# Sheet1.net
KiCad netlist of a schematic drawn in Altium Designer
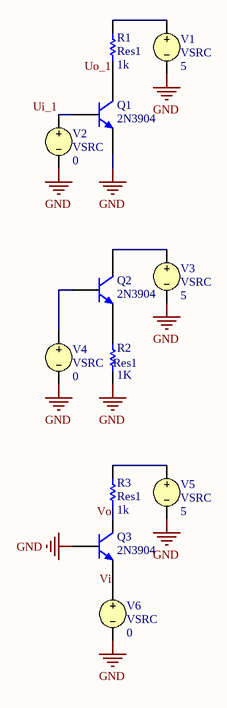
[diagram p0: Sheet1.SchDoc]

(export (version "E")
  (design (tool "Eeschema 10.0.6"))
  (components
    (comp (ref "Q1")
      (value "2N3904")
      (footprint "TO-92A")
      (description "NPN General Purpose Amplifier")
      (fields (field (name "PUBLISHER") "Altium Limited"))
      (libsource (lib "Miscellaneous Devices") (part "2N3904"))
    )
    (comp (ref "Q2")
      (value "2N3904")
      (footprint "TO-92A")
      (description "NPN General Purpose Amplifier")
      (fields (field (name "PUBLISHER") "Altium Limited"))
      (libsource (lib "Miscellaneous Devices") (part "2N3904"))
    )
    (comp (ref "Q3")
      (value "2N3904")
      (footprint "TO-92A")
      (description "NPN General Purpose Amplifier")
      (fields (field (name "PUBLISHER") "Altium Limited"))
      (libsource (lib "Miscellaneous Devices") (part "2N3904"))
    )
    (comp (ref "R1")
      (value "Res1")
      (footprint "AXIAL-0.3")
      (description "Resistor")
      (fields (field (name "ALTIUM_VALUE") "1k") (field (name "PUBLISHER") "Altium Limited"))
      (libsource (lib "Miscellaneous Devices") (part "Res1"))
    )
    (comp (ref "R2")
      (value "Res1")
      (footprint "AXIAL-0.3")
      (description "Resistor")
      (fields (field (name "ALTIUM_VALUE") "1K") (field (name "PUBLISHER") "Altium Limited"))
      (libsource (lib "Miscellaneous Devices") (part "Res1"))
    )
    (comp (ref "R3")
      (value "Res1")
      (footprint "AXIAL-0.3")
      (description "Resistor")
      (fields (field (name "ALTIUM_VALUE") "1k") (field (name "PUBLISHER") "Altium Limited"))
      (libsource (lib "Miscellaneous Devices") (part "Res1"))
    )
    (comp (ref "V1")
      (value "VSRC")
      (description "Voltage Source")
      (fields (field (name "ALTIUM_VALUE") "5") (field (name "PUBLISHER") "Altium Limited"))
      (libsource (lib "Simulation Generic Components") (part "VSRC"))
    )
    (comp (ref "V2")
      (value "VSRC")
      (description "Voltage Source")
      (fields (field (name "DC MAGNITUDE") "0") (field (name "PUBLISHER") "Altium Limited"))
      (libsource (lib "Simulation Generic Components") (part "VSRC"))
    )
    (comp (ref "V3")
      (value "VSRC")
      (description "Voltage Source")
      (fields (field (name "ALTIUM_VALUE") "5") (field (name "PUBLISHER") "Altium Limited"))
      (libsource (lib "Simulation Generic Components") (part "VSRC"))
    )
    (comp (ref "V4")
      (value "VSRC")
      (description "Voltage Source")
      (fields (field (name "DC MAGNITUDE") "0") (field (name "PUBLISHER") "Altium Limited"))
      (libsource (lib "Simulation Generic Components") (part "VSRC"))
    )
    (comp (ref "V5")
      (value "VSRC")
      (description "Voltage Source")
      (fields (field (name "ALTIUM_VALUE") "5") (field (name "PUBLISHER") "Altium Limited"))
      (libsource (lib "Simulation Generic Components") (part "VSRC"))
    )
    (comp (ref "V6")
      (value "VSRC")
      (description "Voltage Source")
      (fields (field (name "DC MAGNITUDE") "0") (field (name "PUBLISHER") "Altium Limited"))
      (libsource (lib "Simulation Generic Components") (part "VSRC"))
    )
  )
  (nets
    (net (code "1") (name "/Ui_1") (class "Default")
      (node (ref "Q1") (pin "2") (pinfunction "B_2") (pintype "passive"))
      (node (ref "V2") (pin "1") (pinfunction "1_1") (pintype "passive"))
    )
    (net (code "2") (name "/Uo_1") (class "Default")
      (node (ref "Q1") (pin "3") (pinfunction "C_3") (pintype "passive"))
      (node (ref "R1") (pin "1") (pinfunction "1_1") (pintype "passive"))
    )
    (net (code "3") (name "/Vi") (class "Default")
      (node (ref "Q3") (pin "1") (pinfunction "E_1") (pintype "passive"))
      (node (ref "V6") (pin "1") (pinfunction "1_1") (pintype "passive"))
    )
    (net (code "4") (name "/Vo") (class "Default")
      (node (ref "Q3") (pin "3") (pinfunction "C_3") (pintype "passive"))
      (node (ref "R3") (pin "1") (pinfunction "1_1") (pintype "passive"))
    )
    (net (code "5") (name "GND") (class "Default")
      (node (ref "Q1") (pin "1") (pinfunction "E_1") (pintype "passive"))
      (node (ref "Q3") (pin "2") (pinfunction "B_2") (pintype "passive"))
      (node (ref "R2") (pin "1") (pinfunction "1_1") (pintype "passive"))
      (node (ref "V1") (pin "2") (pinfunction "2_2") (pintype "passive"))
      (node (ref "V2") (pin "2") (pinfunction "2_2") (pintype "passive"))
      (node (ref "V3") (pin "2") (pinfunction "2_2") (pintype "passive"))
      (node (ref "V4") (pin "2") (pinfunction "2_2") (pintype "passive"))
      (node (ref "V5") (pin "2") (pinfunction "2_2") (pintype "passive"))
      (node (ref "V6") (pin "2") (pinfunction "2_2") (pintype "passive"))
    )
    (net (code "6") (name "Net-(Q2-B)") (class "Default")
      (node (ref "Q2") (pin "2") (pinfunction "B_2") (pintype "passive"))
      (node (ref "V4") (pin "1") (pinfunction "1_1") (pintype "passive"))
    )
    (net (code "7") (name "Net-(Q2-C)") (class "Default")
      (node (ref "Q2") (pin "3") (pinfunction "C_3") (pintype "passive"))
      (node (ref "V3") (pin "1") (pinfunction "1_1") (pintype "passive"))
    )
    (net (code "8") (name "Net-(Q2-E)") (class "Default")
      (node (ref "Q2") (pin "1") (pinfunction "E_1") (pintype "passive"))
      (node (ref "R2") (pin "2") (pinfunction "2_2") (pintype "passive"))
    )
    (net (code "9") (name "Net-(R1-Pad2)") (class "Default")
      (node (ref "R1") (pin "2") (pinfunction "2_2") (pintype "passive"))
      (node (ref "V1") (pin "1") (pinfunction "1_1") (pintype "passive"))
    )
    (net (code "10") (name "Net-(R3-Pad2)") (class "Default")
      (node (ref "R3") (pin "2") (pinfunction "2_2") (pintype "passive"))
      (node (ref "V5") (pin "1") (pinfunction "1_1") (pintype "passive"))
    )
  )
)
